# main.net
KiCad netlist of a schematic drawn in EAGLE
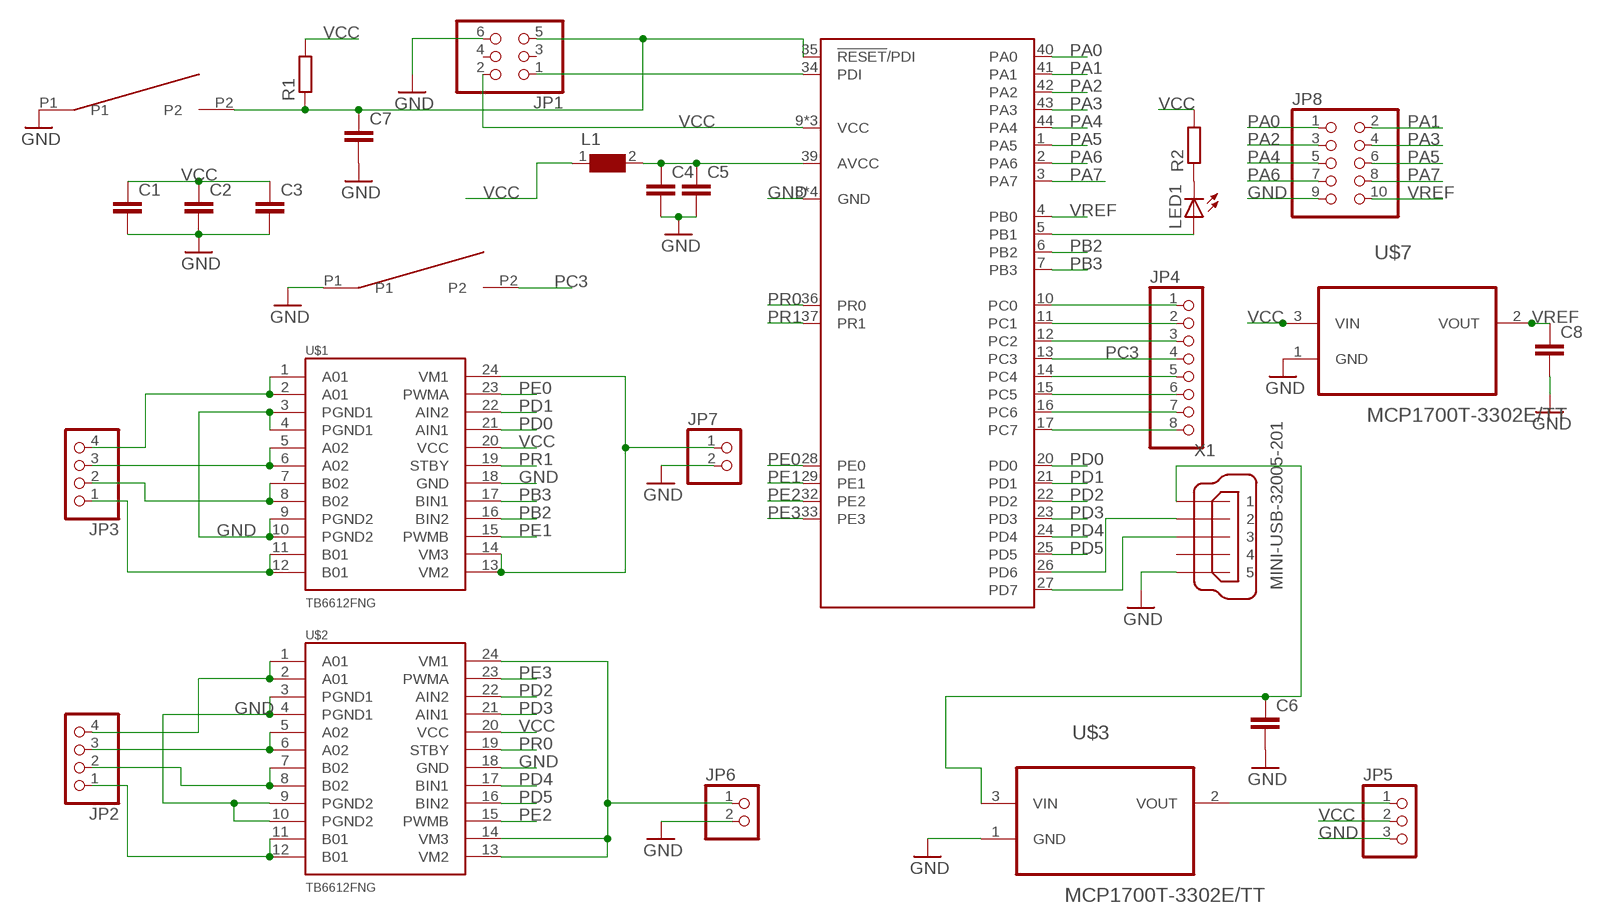
[diagram p0: schematic, sheet 1]

(export (version "E")
  (design (tool "Eeschema 10.0.6"))
  (components
    (comp (ref "C1")
      (value "C-EUC0805")
      (footprint "eagle-import:C0805")
      (libsource (lib "eagle-import") (part "C-EUC0805"))
    )
    (comp (ref "C2")
      (value "C-EUC0805")
      (footprint "eagle-import:C0805")
      (libsource (lib "eagle-import") (part "C-EUC0805"))
    )
    (comp (ref "C3")
      (value "C-EUC0805")
      (footprint "eagle-import:C0805")
      (libsource (lib "eagle-import") (part "C-EUC0805"))
    )
    (comp (ref "C4")
      (value "C-EUC0805")
      (footprint "eagle-import:C0805")
      (libsource (lib "eagle-import") (part "C-EUC0805"))
    )
    (comp (ref "C5")
      (value "C-EUC0805")
      (footprint "eagle-import:C0805")
      (libsource (lib "eagle-import") (part "C-EUC0805"))
    )
    (comp (ref "C6")
      (value "C-EUC0805")
      (footprint "eagle-import:C0805")
      (libsource (lib "eagle-import") (part "C-EUC0805"))
    )
    (comp (ref "C7")
      (value "C-EUC0805")
      (footprint "eagle-import:C0805")
      (libsource (lib "eagle-import") (part "C-EUC0805"))
    )
    (comp (ref "C8")
      (value "C-EUC0805")
      (footprint "eagle-import:C0805")
      (libsource (lib "eagle-import") (part "C-EUC0805"))
    )
    (comp (ref "JP1")
      (value "PINHD-2X3")
      (footprint "eagle-import:2X03")
      (libsource (lib "eagle-import") (part "PINHD-2X3"))
    )
    (comp (ref "JP2")
      (value "PINHD-1X4")
      (footprint "eagle-import:1X04")
      (libsource (lib "eagle-import") (part "PINHD-1X4"))
    )
    (comp (ref "JP3")
      (value "PINHD-1X4")
      (footprint "eagle-import:1X04")
      (libsource (lib "eagle-import") (part "PINHD-1X4"))
    )
    (comp (ref "JP4")
      (value "PINHD-1X8")
      (footprint "eagle-import:1X08")
      (libsource (lib "eagle-import") (part "PINHD-1X8"))
    )
    (comp (ref "JP5")
      (value "PINHD-1X3")
      (footprint "eagle-import:1X03")
      (libsource (lib "eagle-import") (part "PINHD-1X3"))
    )
    (comp (ref "JP6")
      (value "PINHD-1X2")
      (footprint "eagle-import:1X02")
      (libsource (lib "eagle-import") (part "PINHD-1X2"))
    )
    (comp (ref "JP7")
      (value "PINHD-1X2")
      (footprint "eagle-import:1X02")
      (libsource (lib "eagle-import") (part "PINHD-1X2"))
    )
    (comp (ref "JP8")
      (value "PINHD-2X5")
      (footprint "eagle-import:2X05")
      (libsource (lib "eagle-import") (part "PINHD-2X5"))
    )
    (comp (ref "L1")
      (value "WE-CBF-74279202_0805")
      (footprint "eagle-import:0805")
      (fields (field (name "MPN") "74279202"))
      (libsource (lib "eagle-import") (part "WE-CBF_0805-74279202"))
    )
    (comp (ref "LED1")
      (value "LEDCHIP-LED0805")
      (footprint "eagle-import:CHIP-LED0805")
      (libsource (lib "eagle-import") (part "LEDCHIP-LED0805"))
    )
    (comp (ref "R1")
      (value "R-EU_R0805")
      (footprint "eagle-import:R0805")
      (libsource (lib "eagle-import") (part "R-EU_R0805"))
    )
    (comp (ref "R2")
      (value "R-EU_R0805")
      (footprint "eagle-import:R0805")
      (libsource (lib "eagle-import") (part "R-EU_R0805"))
    )
    (comp (ref "U$1")
      (value "TB6612FNG")
      (footprint "eagle-import:SSOP24")
      (libsource (lib "eagle-import") (part "TB6612FNG"))
    )
    (comp (ref "U$2")
      (value "TB6612FNG")
      (footprint "eagle-import:SSOP24")
      (libsource (lib "eagle-import") (part "TB6612FNG"))
    )
    (comp (ref "U$3")
      (value "MCP1700T-3302E/TT")
      (footprint "eagle-import:SOT95P237X112-3N")
      (libsource (lib "eagle-import") (part "MCP1700T-3302E/TT"))
    )
    (comp (ref "U$4")
      (value "SWITCH_2PIN_SMD")
      (footprint "eagle-import:SWITCH_2PIN_SMD")
      (libsource (lib "eagle-import") (part "SWITCH_2PIN_SMD"))
    )
    (comp (ref "U$6")
      (value "SWITCH_2PIN_SMD")
      (footprint "eagle-import:SWITCH_2PIN_SMD")
      (libsource (lib "eagle-import") (part "SWITCH_2PIN_SMD"))
    )
    (comp (ref "U$7")
      (value "MCP1700T-3302E/TT")
      (footprint "eagle-import:SOT95P237X112-3N")
      (libsource (lib "eagle-import") (part "MCP1700T-3302E/TT"))
    )
    (comp (ref "U1")
      (value "ATXMEGA32C4-AU")
      (footprint "eagle-import:TQFP-44A-44")
      (libsource (lib "eagle-import") (part "ATXMEGA32C4-AU"))
    )
    (comp (ref "X1")
      (value "MINI-USB-32005-201")
      (footprint "eagle-import:32005-201")
      (libsource (lib "eagle-import") (part "MINI-USB-32005-201"))
    )
  )
  (nets
    (net (code "1") (name "/PA0") (class "Default")
      (node (ref "JP8") (pin "1") (pinfunction "1_1") (pintype "passive"))
      (node (ref "U1") (pin "40") (pinfunction "PA0_40") (pintype "bidirectional"))
    )
    (net (code "2") (name "/PA1") (class "Default")
      (node (ref "JP8") (pin "2") (pinfunction "2_2") (pintype "passive"))
      (node (ref "U1") (pin "41") (pinfunction "PA1_41") (pintype "bidirectional"))
    )
    (net (code "3") (name "/PA2") (class "Default")
      (node (ref "JP8") (pin "3") (pinfunction "3_3") (pintype "passive"))
      (node (ref "U1") (pin "42") (pinfunction "PA2_42") (pintype "bidirectional"))
    )
    (net (code "4") (name "/PA3") (class "Default")
      (node (ref "JP8") (pin "4") (pinfunction "4_4") (pintype "passive"))
      (node (ref "U1") (pin "43") (pinfunction "PA3_43") (pintype "bidirectional"))
    )
    (net (code "5") (name "/PA4") (class "Default")
      (node (ref "JP8") (pin "5") (pinfunction "5_5") (pintype "passive"))
      (node (ref "U1") (pin "44") (pinfunction "PA4_44") (pintype "bidirectional"))
    )
    (net (code "6") (name "/PA5") (class "Default")
      (node (ref "JP8") (pin "6") (pinfunction "6_6") (pintype "passive"))
      (node (ref "U1") (pin "1") (pinfunction "PA5_1") (pintype "bidirectional"))
    )
    (net (code "7") (name "/PA6") (class "Default")
      (node (ref "JP8") (pin "7") (pinfunction "7_7") (pintype "passive"))
      (node (ref "U1") (pin "2") (pinfunction "PA6_2") (pintype "bidirectional"))
    )
    (net (code "8") (name "/PA7") (class "Default")
      (node (ref "JP8") (pin "8") (pinfunction "8_8") (pintype "passive"))
      (node (ref "U1") (pin "3") (pinfunction "PA7_3") (pintype "bidirectional"))
    )
    (net (code "9") (name "/PB2") (class "Default")
      (node (ref "U$1") (pin "16") (pinfunction "BIN2_16") (pintype "bidirectional"))
      (node (ref "U1") (pin "6") (pinfunction "PB2_6") (pintype "bidirectional"))
    )
    (net (code "10") (name "/PB3") (class "Default")
      (node (ref "U$1") (pin "17") (pinfunction "BIN1_17") (pintype "bidirectional"))
      (node (ref "U1") (pin "7") (pinfunction "PB3_7") (pintype "bidirectional"))
    )
    (net (code "11") (name "/PC3") (class "Default")
      (node (ref "JP4") (pin "4") (pinfunction "4_4") (pintype "passive"))
      (node (ref "U$6") (pin "P2") (pinfunction "P2_P2") (pintype "bidirectional"))
      (node (ref "U1") (pin "13") (pinfunction "PC3_13") (pintype "bidirectional"))
    )
    (net (code "12") (name "/PD0") (class "Default")
      (node (ref "U$1") (pin "21") (pinfunction "AIN1_21") (pintype "bidirectional"))
      (node (ref "U1") (pin "20") (pinfunction "PD0_20") (pintype "bidirectional"))
    )
    (net (code "13") (name "/PD1") (class "Default")
      (node (ref "U$1") (pin "22") (pinfunction "AIN2_22") (pintype "bidirectional"))
      (node (ref "U1") (pin "21") (pinfunction "PD1_21") (pintype "bidirectional"))
    )
    (net (code "14") (name "/PD2") (class "Default")
      (node (ref "U$2") (pin "22") (pinfunction "AIN2_22") (pintype "bidirectional"))
      (node (ref "U1") (pin "22") (pinfunction "PD2_22") (pintype "bidirectional"))
    )
    (net (code "15") (name "/PD3") (class "Default")
      (node (ref "U$2") (pin "21") (pinfunction "AIN1_21") (pintype "bidirectional"))
      (node (ref "U1") (pin "23") (pinfunction "PD3_23") (pintype "bidirectional"))
    )
    (net (code "16") (name "/PD4") (class "Default")
      (node (ref "U$2") (pin "17") (pinfunction "BIN1_17") (pintype "bidirectional"))
      (node (ref "U1") (pin "24") (pinfunction "PD4_24") (pintype "bidirectional"))
    )
    (net (code "17") (name "/PD5") (class "Default")
      (node (ref "U$2") (pin "16") (pinfunction "BIN2_16") (pintype "bidirectional"))
      (node (ref "U1") (pin "25") (pinfunction "PD5_25") (pintype "bidirectional"))
    )
    (net (code "18") (name "/PE0") (class "Default")
      (node (ref "U$1") (pin "23") (pinfunction "PWMA_23") (pintype "bidirectional"))
      (node (ref "U1") (pin "28") (pinfunction "PE0_28") (pintype "bidirectional"))
    )
    (net (code "19") (name "/PE1") (class "Default")
      (node (ref "U$1") (pin "15") (pinfunction "PWMB_15") (pintype "bidirectional"))
      (node (ref "U1") (pin "29") (pinfunction "PE1_29") (pintype "bidirectional"))
    )
    (net (code "20") (name "/PE2") (class "Default")
      (node (ref "U$2") (pin "15") (pinfunction "PWMB_15") (pintype "bidirectional"))
      (node (ref "U1") (pin "32") (pinfunction "PE2_32") (pintype "bidirectional"))
    )
    (net (code "21") (name "/PE3") (class "Default")
      (node (ref "U$2") (pin "23") (pinfunction "PWMA_23") (pintype "bidirectional"))
      (node (ref "U1") (pin "33") (pinfunction "PE3_33") (pintype "bidirectional"))
    )
    (net (code "22") (name "/PR0") (class "Default")
      (node (ref "U$2") (pin "19") (pinfunction "STBY_19") (pintype "bidirectional"))
      (node (ref "U1") (pin "36") (pinfunction "PR0_36") (pintype "bidirectional"))
    )
    (net (code "23") (name "/PR1") (class "Default")
      (node (ref "U$1") (pin "19") (pinfunction "STBY_19") (pintype "bidirectional"))
      (node (ref "U1") (pin "37") (pinfunction "PR1_37") (pintype "bidirectional"))
    )
    (net (code "24") (name "/VCC") (class "Default")
      (node (ref "C1") (pin "1") (pinfunction "1_1") (pintype "passive"))
      (node (ref "C2") (pin "1") (pinfunction "1_1") (pintype "passive"))
      (node (ref "C3") (pin "1") (pinfunction "1_1") (pintype "passive"))
      (node (ref "JP1") (pin "2") (pinfunction "2_2") (pintype "passive"))
      (node (ref "JP5") (pin "2") (pinfunction "2_2") (pintype "passive"))
      (node (ref "L1") (pin "1") (pinfunction "1_1") (pintype "passive"))
      (node (ref "R1") (pin "2") (pinfunction "2_2") (pintype "passive"))
      (node (ref "R2") (pin "2") (pinfunction "2_2") (pintype "passive"))
      (node (ref "U$1") (pin "20") (pinfunction "VCC_20") (pintype "bidirectional"))
      (node (ref "U$2") (pin "20") (pinfunction "VCC_20") (pintype "bidirectional"))
      (node (ref "U$7") (pin "3") (pinfunction "VIN_3") (pintype "input"))
      (node (ref "U1") (pin "19") (pinfunction "VCC_19") (pintype "power_in"))
      (node (ref "U1") (pin "31") (pinfunction "VCC_31") (pintype "power_in"))
      (node (ref "U1") (pin "9") (pinfunction "VCC_9") (pintype "power_in"))
    )
    (net (code "25") (name "/VREF") (class "Default")
      (node (ref "C8") (pin "1") (pinfunction "1_1") (pintype "passive"))
      (node (ref "JP8") (pin "10") (pinfunction "10_10") (pintype "passive"))
      (node (ref "U$7") (pin "2") (pinfunction "VOUT_2") (pintype "output"))
      (node (ref "U1") (pin "4") (pinfunction "PB0_4") (pintype "bidirectional"))
    )
    (net (code "26") (name "GND") (class "Default")
      (node (ref "C1") (pin "2") (pinfunction "2_2") (pintype "passive"))
      (node (ref "C2") (pin "2") (pinfunction "2_2") (pintype "passive"))
      (node (ref "C3") (pin "2") (pinfunction "2_2") (pintype "passive"))
      (node (ref "C4") (pin "2") (pinfunction "2_2") (pintype "passive"))
      (node (ref "C5") (pin "2") (pinfunction "2_2") (pintype "passive"))
      (node (ref "C6") (pin "2") (pinfunction "2_2") (pintype "passive"))
      (node (ref "C7") (pin "2") (pinfunction "2_2") (pintype "passive"))
      (node (ref "C8") (pin "2") (pinfunction "2_2") (pintype "passive"))
      (node (ref "JP1") (pin "6") (pinfunction "6_6") (pintype "passive"))
      (node (ref "JP5") (pin "3") (pinfunction "3_3") (pintype "passive"))
      (node (ref "JP6") (pin "2") (pinfunction "2_2") (pintype "passive"))
      (node (ref "JP7") (pin "2") (pinfunction "2_2") (pintype "passive"))
      (node (ref "JP8") (pin "9") (pinfunction "9_9") (pintype "passive"))
      (node (ref "U$1") (pin "10") (pinfunction "PGND2_10") (pintype "bidirectional"))
      (node (ref "U$1") (pin "18") (pinfunction "GND_18") (pintype "bidirectional"))
      (node (ref "U$1") (pin "3") (pinfunction "PGND1_3") (pintype "bidirectional"))
      (node (ref "U$1") (pin "4") (pinfunction "PGND1_4") (pintype "bidirectional"))
      (node (ref "U$1") (pin "9") (pinfunction "PGND2_9") (pintype "bidirectional"))
      (node (ref "U$2") (pin "10") (pinfunction "PGND2_10") (pintype "bidirectional"))
      (node (ref "U$2") (pin "18") (pinfunction "GND_18") (pintype "bidirectional"))
      (node (ref "U$2") (pin "3") (pinfunction "PGND1_3") (pintype "bidirectional"))
      (node (ref "U$2") (pin "4") (pinfunction "PGND1_4") (pintype "bidirectional"))
      (node (ref "U$2") (pin "9") (pinfunction "PGND2_9") (pintype "bidirectional"))
      (node (ref "U$3") (pin "1") (pinfunction "GND_1") (pintype "passive"))
      (node (ref "U$4") (pin "P1") (pinfunction "P1_P1") (pintype "bidirectional"))
      (node (ref "U$6") (pin "P1") (pinfunction "P1_P1") (pintype "bidirectional"))
      (node (ref "U$7") (pin "1") (pinfunction "GND_1") (pintype "passive"))
      (node (ref "U1") (pin "18") (pinfunction "GND_18") (pintype "power_in"))
      (node (ref "U1") (pin "30") (pinfunction "GND_30") (pintype "power_in"))
      (node (ref "U1") (pin "38") (pinfunction "GND_38") (pintype "power_in"))
      (node (ref "U1") (pin "8") (pinfunction "GND_8") (pintype "power_in"))
      (node (ref "X1") (pin "5") (pinfunction "5_5") (pintype "passive"))
    )
    (net (code "27") (name "Net-(JP2-Pad1)") (class "Default")
      (node (ref "JP2") (pin "1") (pinfunction "1_1") (pintype "passive"))
      (node (ref "U$2") (pin "11") (pinfunction "B01_11") (pintype "bidirectional"))
      (node (ref "U$2") (pin "12") (pinfunction "B01_12") (pintype "bidirectional"))
    )
    (net (code "28") (name "Net-(JP2-Pad2)") (class "Default")
      (node (ref "JP2") (pin "2") (pinfunction "2_2") (pintype "passive"))
      (node (ref "U$2") (pin "7") (pinfunction "B02_7") (pintype "bidirectional"))
      (node (ref "U$2") (pin "8") (pinfunction "B02_8") (pintype "bidirectional"))
    )
    (net (code "29") (name "Net-(JP2-Pad3)") (class "Default")
      (node (ref "JP2") (pin "3") (pinfunction "3_3") (pintype "passive"))
      (node (ref "U$2") (pin "5") (pinfunction "A02_5") (pintype "bidirectional"))
      (node (ref "U$2") (pin "6") (pinfunction "A02_6") (pintype "bidirectional"))
    )
    (net (code "30") (name "Net-(JP2-Pad4)") (class "Default")
      (node (ref "JP2") (pin "4") (pinfunction "4_4") (pintype "passive"))
      (node (ref "U$2") (pin "1") (pinfunction "A01_1") (pintype "bidirectional"))
      (node (ref "U$2") (pin "2") (pinfunction "A01_2") (pintype "bidirectional"))
    )
    (net (code "31") (name "Net-(JP3-Pad1)") (class "Default")
      (node (ref "JP3") (pin "1") (pinfunction "1_1") (pintype "passive"))
      (node (ref "U$1") (pin "11") (pinfunction "B01_11") (pintype "bidirectional"))
      (node (ref "U$1") (pin "12") (pinfunction "B01_12") (pintype "bidirectional"))
    )
    (net (code "32") (name "Net-(JP3-Pad2)") (class "Default")
      (node (ref "JP3") (pin "2") (pinfunction "2_2") (pintype "passive"))
      (node (ref "U$1") (pin "7") (pinfunction "B02_7") (pintype "bidirectional"))
      (node (ref "U$1") (pin "8") (pinfunction "B02_8") (pintype "bidirectional"))
    )
    (net (code "33") (name "Net-(JP3-Pad3)") (class "Default")
      (node (ref "JP3") (pin "3") (pinfunction "3_3") (pintype "passive"))
      (node (ref "U$1") (pin "5") (pinfunction "A02_5") (pintype "bidirectional"))
      (node (ref "U$1") (pin "6") (pinfunction "A02_6") (pintype "bidirectional"))
    )
    (net (code "34") (name "Net-(JP3-Pad4)") (class "Default")
      (node (ref "JP3") (pin "4") (pinfunction "4_4") (pintype "passive"))
      (node (ref "U$1") (pin "1") (pinfunction "A01_1") (pintype "bidirectional"))
      (node (ref "U$1") (pin "2") (pinfunction "A01_2") (pintype "bidirectional"))
    )
    (net (code "35") (name "Net-(LED1-PadC)") (class "Default")
      (node (ref "LED1") (pin "C") (pinfunction "C_C") (pintype "passive"))
      (node (ref "R2") (pin "1") (pinfunction "1_1") (pintype "passive"))
    )
    (net (code "36") (name "Net-(U$1-VM1)") (class "Default")
      (node (ref "JP7") (pin "1") (pinfunction "1_1") (pintype "passive"))
      (node (ref "U$1") (pin "13") (pinfunction "VM2_13") (pintype "bidirectional"))
      (node (ref "U$1") (pin "14") (pinfunction "VM3_14") (pintype "bidirectional"))
      (node (ref "U$1") (pin "24") (pinfunction "VM1_24") (pintype "bidirectional"))
    )
    (net (code "37") (name "Net-(U$2-VM1)") (class "Default")
      (node (ref "JP6") (pin "1") (pinfunction "1_1") (pintype "passive"))
      (node (ref "U$2") (pin "13") (pinfunction "VM2_13") (pintype "bidirectional"))
      (node (ref "U$2") (pin "14") (pinfunction "VM3_14") (pintype "bidirectional"))
      (node (ref "U$2") (pin "24") (pinfunction "VM1_24") (pintype "bidirectional"))
    )
    (net (code "38") (name "Net-(U$3-VIN)") (class "Default")
      (node (ref "C6") (pin "1") (pinfunction "1_1") (pintype "passive"))
      (node (ref "U$3") (pin "3") (pinfunction "VIN_3") (pintype "input"))
      (node (ref "X1") (pin "1") (pinfunction "1_1") (pintype "passive"))
    )
    (net (code "39") (name "Net-(U$3-VOUT)") (class "Default")
      (node (ref "JP5") (pin "1") (pinfunction "1_1") (pintype "passive"))
      (node (ref "U$3") (pin "2") (pinfunction "VOUT_2") (pintype "output"))
    )
    (net (code "40") (name "Net-(U1-AVCC)") (class "Default")
      (node (ref "C4") (pin "1") (pinfunction "1_1") (pintype "passive"))
      (node (ref "C5") (pin "1") (pinfunction "1_1") (pintype "passive"))
      (node (ref "L1") (pin "2") (pinfunction "2_2") (pintype "passive"))
      (node (ref "U1") (pin "39") (pinfunction "AVCC_39") (pintype "power_in"))
    )
    (net (code "41") (name "Net-(U1-PB1)") (class "Default")
      (node (ref "LED1") (pin "A") (pinfunction "A_A") (pintype "passive"))
      (node (ref "U1") (pin "5") (pinfunction "PB1_5") (pintype "bidirectional"))
    )
    (net (code "42") (name "Net-(U1-PC0)") (class "Default")
      (node (ref "JP4") (pin "1") (pinfunction "1_1") (pintype "passive"))
      (node (ref "U1") (pin "10") (pinfunction "PC0_10") (pintype "bidirectional"))
    )
    (net (code "43") (name "Net-(U1-PC1)") (class "Default")
      (node (ref "JP4") (pin "2") (pinfunction "2_2") (pintype "passive"))
      (node (ref "U1") (pin "11") (pinfunction "PC1_11") (pintype "bidirectional"))
    )
    (net (code "44") (name "Net-(U1-PC2)") (class "Default")
      (node (ref "JP4") (pin "3") (pinfunction "3_3") (pintype "passive"))
      (node (ref "U1") (pin "12") (pinfunction "PC2_12") (pintype "bidirectional"))
    )
    (net (code "45") (name "Net-(U1-PC4)") (class "Default")
      (node (ref "JP4") (pin "5") (pinfunction "5_5") (pintype "passive"))
      (node (ref "U1") (pin "14") (pinfunction "PC4_14") (pintype "bidirectional"))
    )
    (net (code "46") (name "Net-(U1-PC5)") (class "Default")
      (node (ref "JP4") (pin "6") (pinfunction "6_6") (pintype "passive"))
      (node (ref "U1") (pin "15") (pinfunction "PC5_15") (pintype "bidirectional"))
    )
    (net (code "47") (name "Net-(U1-PC6)") (class "Default")
      (node (ref "JP4") (pin "7") (pinfunction "7_7") (pintype "passive"))
      (node (ref "U1") (pin "16") (pinfunction "PC6_16") (pintype "bidirectional"))
    )
    (net (code "48") (name "Net-(U1-PC7)") (class "Default")
      (node (ref "JP4") (pin "8") (pinfunction "8_8") (pintype "passive"))
      (node (ref "U1") (pin "17") (pinfunction "PC7_17") (pintype "bidirectional"))
    )
    (net (code "49") (name "Net-(U1-PD6)") (class "Default")
      (node (ref "U1") (pin "26") (pinfunction "PD6_26") (pintype "bidirectional"))
      (node (ref "X1") (pin "2") (pinfunction "2_2") (pintype "passive"))
    )
    (net (code "50") (name "Net-(U1-PD7)") (class "Default")
      (node (ref "U1") (pin "27") (pinfunction "PD7_27") (pintype "bidirectional"))
      (node (ref "X1") (pin "3") (pinfunction "3_3") (pintype "passive"))
    )
    (net (code "51") (name "Net-(U1-PDI)") (class "Default")
      (node (ref "JP1") (pin "1") (pinfunction "1_1") (pintype "passive"))
      (node (ref "U1") (pin "34") (pinfunction "PDI_34") (pintype "bidirectional"))
    )
    (net (code "52") (name "Net-(U1-~{RESET}{slash}PDI)") (class "Default")
      (node (ref "C7") (pin "1") (pinfunction "1_1") (pintype "passive"))
      (node (ref "JP1") (pin "5") (pinfunction "5_5") (pintype "passive"))
      (node (ref "R1") (pin "1") (pinfunction "1_1") (pintype "passive"))
      (node (ref "U$4") (pin "P2") (pinfunction "P2_P2") (pintype "bidirectional"))
      (node (ref "U1") (pin "35") (pinfunction "~{RESET}/PDI_35") (pintype "bidirectional"))
    )
    (net (code "53") (name "unconnected-(JP1-Pad3)") (class "Default")
      (node (ref "JP1") (pin "3") (pinfunction "3_3") (pintype "passive"))
    )
    (net (code "54") (name "unconnected-(JP1-Pad4)") (class "Default")
      (node (ref "JP1") (pin "4") (pinfunction "4_4") (pintype "passive"))
    )
    (net (code "55") (name "unconnected-(X1-Pad4)") (class "Default")
      (node (ref "X1") (pin "4") (pinfunction "4_4") (pintype "passive"))
    )
  )
)
